# Filter_Bank_EVB.net
KiCad netlist of a schematic drawn in Altium Designer
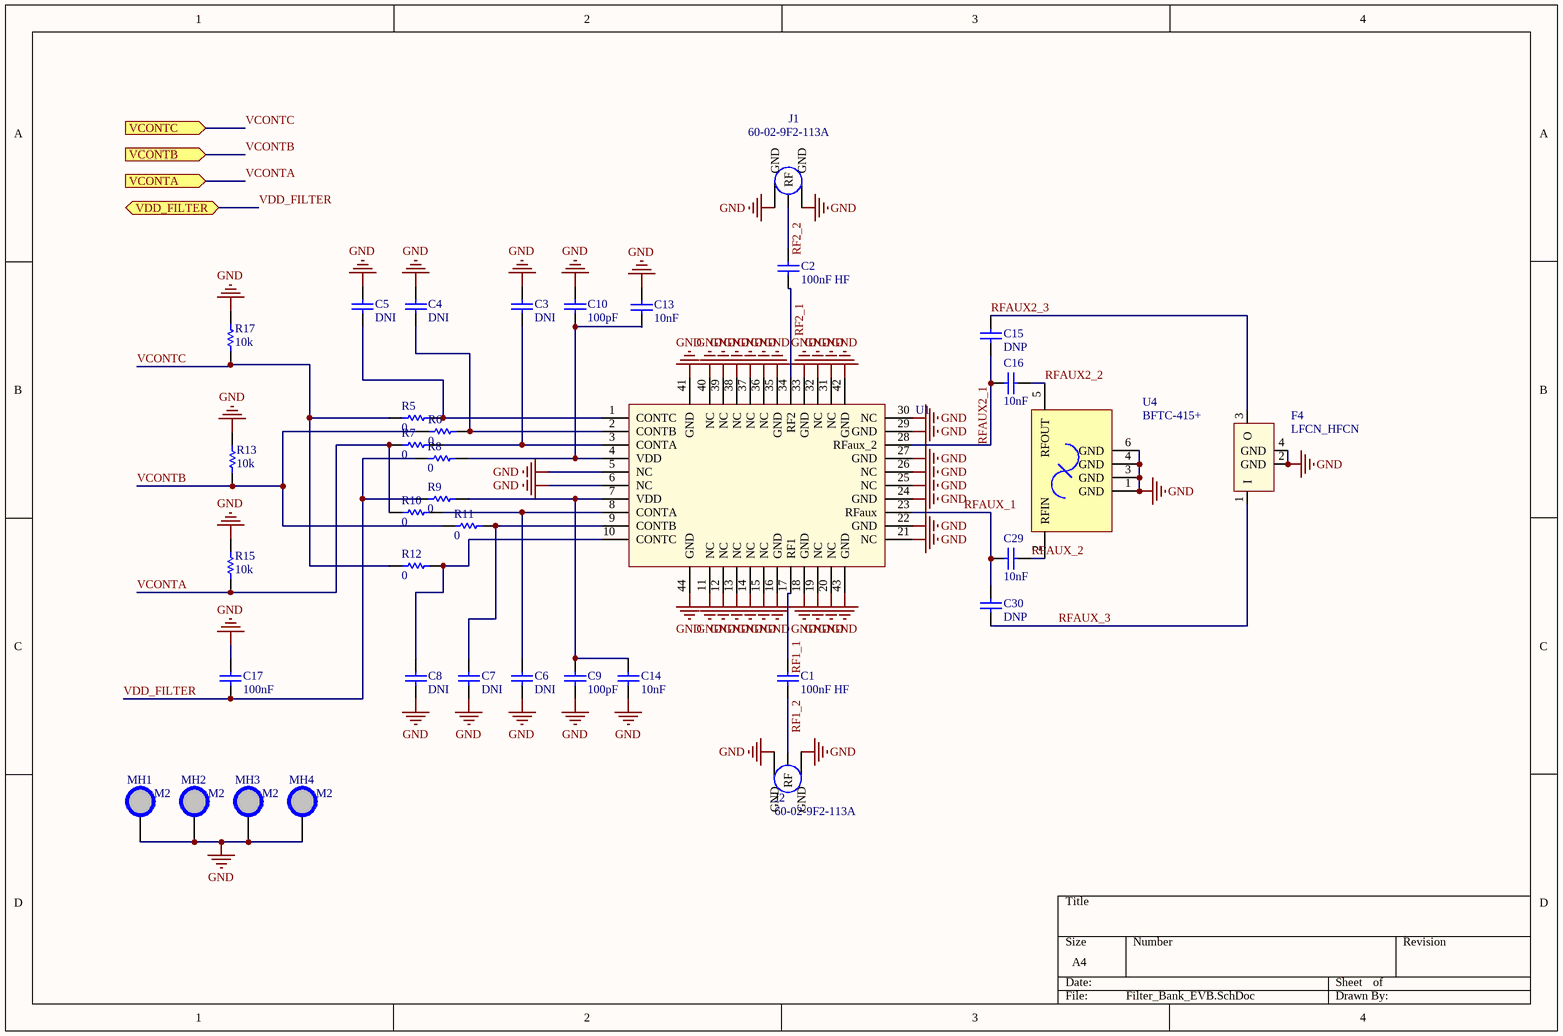
[diagram p0: Filter_Bank_EVB.SchDoc]

(export (version "E")
  (design (tool "Eeschema 10.0.6"))
  (components
    (comp (ref "C1")
      (value "100nF HF")
      (footprint "C0402")
      (description "Capacitor")
      (fields (field (name "Comment") "CAP"))
      (libsource (lib "ATEK") (part "CAP"))
    )
    (comp (ref "C2")
      (value "100nF HF")
      (footprint "C0402")
      (description "Capacitor")
      (fields (field (name "Comment") "CAP"))
      (libsource (lib "ATEK") (part "CAP"))
    )
    (comp (ref "C3")
      (value "DNI")
      (footprint "C0402")
      (description "Capacitor")
      (fields (field (name "Comment") "CAP"))
      (libsource (lib "ATEK") (part "CAP"))
    )
    (comp (ref "C4")
      (value "DNI")
      (footprint "C0402")
      (description "Capacitor")
      (fields (field (name "Comment") "CAP"))
      (libsource (lib "ATEK") (part "CAP"))
    )
    (comp (ref "C5")
      (value "DNI")
      (footprint "C0402")
      (description "Capacitor")
      (fields (field (name "Comment") "CAP"))
      (libsource (lib "ATEK") (part "CAP"))
    )
    (comp (ref "C6")
      (value "DNI")
      (footprint "C0402")
      (description "Capacitor")
      (fields (field (name "Comment") "CAP"))
      (libsource (lib "ATEK") (part "CAP"))
    )
    (comp (ref "C7")
      (value "DNI")
      (footprint "C0402")
      (description "Capacitor")
      (fields (field (name "Comment") "CAP"))
      (libsource (lib "ATEK") (part "CAP"))
    )
    (comp (ref "C8")
      (value "DNI")
      (footprint "C0402")
      (description "Capacitor")
      (fields (field (name "Comment") "CAP"))
      (libsource (lib "ATEK") (part "CAP"))
    )
    (comp (ref "C9")
      (value "100pF")
      (footprint "C0402")
      (description "Capacitor")
      (fields (field (name "Comment") "CAP"))
      (libsource (lib "ATEK") (part "CAP"))
    )
    (comp (ref "C10")
      (value "100pF")
      (footprint "C0402")
      (description "Capacitor")
      (fields (field (name "Comment") "CAP"))
      (libsource (lib "ATEK") (part "CAP"))
    )
    (comp (ref "C13")
      (value "10nF")
      (footprint "C0402")
      (description "Capacitor")
      (fields (field (name "Comment") "CAP"))
      (libsource (lib "ATEK") (part "CAP"))
    )
    (comp (ref "C14")
      (value "10nF")
      (footprint "C0402")
      (description "Capacitor")
      (fields (field (name "Comment") "CAP"))
      (libsource (lib "ATEK") (part "CAP"))
    )
    (comp (ref "C15")
      (value "DNP")
      (footprint "C0402")
      (description "Capacitor")
      (fields (field (name "Comment") "CAP"))
      (libsource (lib "ATEK") (part "CAP"))
    )
    (comp (ref "C16")
      (value "10nF")
      (footprint "C0402")
      (description "Capacitor")
      (fields (field (name "Comment") "CAP"))
      (libsource (lib "ATEK") (part "CAP"))
    )
    (comp (ref "C17")
      (value "100nF")
      (footprint "C0402")
      (description "Capacitor")
      (fields (field (name "Comment") "CAP"))
      (libsource (lib "ATEK") (part "CAP"))
    )
    (comp (ref "C29")
      (value "10nF")
      (footprint "C0402")
      (description "Capacitor")
      (fields (field (name "Comment") "CAP"))
      (libsource (lib "ATEK") (part "CAP"))
    )
    (comp (ref "C30")
      (value "DNP")
      (footprint "C0402")
      (description "Capacitor")
      (fields (field (name "Comment") "CAP"))
      (libsource (lib "ATEK") (part "CAP"))
    )
    (comp (ref "F4") (value "LFCN_HFCN") (footprint "FV1206") (libsource (lib "ATEK") (part "LFCN_HFCN")))
    (comp (ref "J1")
      (value "60-02-9F2-113A")
      (footprint "60-02-9F2-113A")
      (libsource (lib "ATEK") (part "60-02-9F2-113A"))
    )
    (comp (ref "J2")
      (value "60-02-9F2-113A")
      (footprint "60-02-9F2-113A")
      (libsource (lib "ATEK") (part "60-02-9F2-113A"))
    )
    (comp (ref "MH1") (value "M2") (footprint "M2") (libsource (lib "ATEK") (part "M2")))
    (comp (ref "MH2") (value "M2") (footprint "M2") (libsource (lib "ATEK") (part "M2")))
    (comp (ref "MH3") (value "M2") (footprint "M2") (libsource (lib "ATEK") (part "M2")))
    (comp (ref "MH4") (value "M2") (footprint "M2") (libsource (lib "ATEK") (part "M2")))
    (comp (ref "R5")
      (value "0")
      (footprint "R0402")
      (description "Resistor")
      (fields (field (name "Comment") "RES"))
      (libsource (lib "ATEK") (part "RES"))
    )
    (comp (ref "R6")
      (value "0")
      (footprint "R0402")
      (description "Resistor")
      (fields (field (name "Comment") "RES"))
      (libsource (lib "ATEK") (part "RES"))
    )
    (comp (ref "R7")
      (value "0")
      (footprint "R0402")
      (description "Resistor")
      (fields (field (name "Comment") "RES"))
      (libsource (lib "ATEK") (part "RES"))
    )
    (comp (ref "R8")
      (value "0")
      (footprint "R0402")
      (description "Resistor")
      (fields (field (name "Comment") "RES"))
      (libsource (lib "ATEK") (part "RES"))
    )
    (comp (ref "R9")
      (value "0")
      (footprint "R0402")
      (description "Resistor")
      (fields (field (name "Comment") "RES"))
      (libsource (lib "ATEK") (part "RES"))
    )
    (comp (ref "R10")
      (value "0")
      (footprint "R0402")
      (description "Resistor")
      (fields (field (name "Comment") "RES"))
      (libsource (lib "ATEK") (part "RES"))
    )
    (comp (ref "R11")
      (value "0")
      (footprint "R0402")
      (description "Resistor")
      (fields (field (name "Comment") "RES"))
      (libsource (lib "ATEK") (part "RES"))
    )
    (comp (ref "R12")
      (value "0")
      (footprint "R0402")
      (description "Resistor")
      (fields (field (name "Comment") "RES"))
      (libsource (lib "ATEK") (part "RES"))
    )
    (comp (ref "R13")
      (value "10k")
      (footprint "R0402")
      (description "Resistor")
      (fields (field (name "Comment") "RES"))
      (libsource (lib "ATEK") (part "RES"))
    )
    (comp (ref "R15")
      (value "10k")
      (footprint "R0402")
      (description "Resistor")
      (fields (field (name "Comment") "RES"))
      (libsource (lib "ATEK") (part "RES"))
    )
    (comp (ref "R17")
      (value "10k")
      (footprint "R0402")
      (description "Resistor")
      (fields (field (name "Comment") "RES"))
      (libsource (lib "ATEK") (part "RES"))
    )
    (comp (ref "U1")
      (value "Bypass LNA")
      (footprint "40L-QFN-6X6-50P-MOD")
      (libsource (lib "ATEK") (part "Filter_Bank"))
    )
    (comp (ref "U4") (value "BFTC-415+") (footprint "BFTC-415+") (libsource (lib "ATEK") (part "BFTC-415+")))
  )
  (nets
    (net (code "1") (name "/RF1_1") (class "Default")
      (node (ref "C1") (pin "2") (pinfunction "2_2") (pintype "passive"))
      (node (ref "U1") (pin "17") (pinfunction "RF1_17") (pintype "passive"))
    )
    (net (code "2") (name "/RF1_2") (class "Default")
      (node (ref "C1") (pin "1") (pinfunction "1_1") (pintype "passive"))
      (node (ref "J2") (pin "1") (pinfunction "RF_1") (pintype "passive"))
    )
    (net (code "3") (name "/RF2_1") (class "Default")
      (node (ref "C2") (pin "1") (pinfunction "1_1") (pintype "passive"))
      (node (ref "U1") (pin "34") (pinfunction "RF2_34") (pintype "passive"))
    )
    (net (code "4") (name "/RF2_2") (class "Default")
      (node (ref "C2") (pin "2") (pinfunction "2_2") (pintype "passive"))
      (node (ref "J1") (pin "1") (pinfunction "RF_1") (pintype "passive"))
    )
    (net (code "5") (name "/RFAUX2_1") (class "Default")
      (node (ref "C15") (pin "2") (pinfunction "2_2") (pintype "passive"))
      (node (ref "C16") (pin "2") (pinfunction "2_2") (pintype "passive"))
      (node (ref "U1") (pin "28") (pinfunction "RFaux_2_28") (pintype "passive"))
    )
    (net (code "6") (name "/RFAUX2_2") (class "Default")
      (node (ref "C16") (pin "1") (pinfunction "1_1") (pintype "passive"))
      (node (ref "U4") (pin "5") (pinfunction "RFOUT_5") (pintype "passive"))
    )
    (net (code "7") (name "/RFAUX2_3") (class "Default")
      (node (ref "C15") (pin "1") (pinfunction "1_1") (pintype "passive"))
      (node (ref "F4") (pin "3") (pinfunction "O_3") (pintype "passive"))
    )
    (net (code "8") (name "/RFAUX_1") (class "Default")
      (node (ref "C29") (pin "2") (pinfunction "2_2") (pintype "passive"))
      (node (ref "C30") (pin "1") (pinfunction "1_1") (pintype "passive"))
      (node (ref "U1") (pin "23") (pinfunction "RFaux_23") (pintype "passive"))
    )
    (net (code "9") (name "/RFAUX_2") (class "Default")
      (node (ref "C29") (pin "1") (pinfunction "1_1") (pintype "passive"))
      (node (ref "U4") (pin "2") (pinfunction "RFIN_2") (pintype "passive"))
    )
    (net (code "10") (name "/RFAUX_3") (class "Default")
      (node (ref "C30") (pin "2") (pinfunction "2_2") (pintype "passive"))
      (node (ref "F4") (pin "1") (pinfunction "I_1") (pintype "passive"))
    )
    (net (code "11") (name "/VCONTA") (class "Default")
      (node (ref "R10") (pin "1") (pinfunction "1_1") (pintype "passive"))
      (node (ref "R15") (pin "1") (pinfunction "1_1") (pintype "passive"))
      (node (ref "R7") (pin "1") (pinfunction "1_1") (pintype "passive"))
    )
    (net (code "12") (name "/VCONTB") (class "Default")
      (node (ref "R11") (pin "1") (pinfunction "1_1") (pintype "passive"))
      (node (ref "R13") (pin "1") (pinfunction "1_1") (pintype "passive"))
      (node (ref "R6") (pin "1") (pinfunction "1_1") (pintype "passive"))
    )
    (net (code "13") (name "/VCONTC") (class "Default")
      (node (ref "R12") (pin "1") (pinfunction "1_1") (pintype "passive"))
      (node (ref "R17") (pin "1") (pinfunction "1_1") (pintype "passive"))
      (node (ref "R5") (pin "1") (pinfunction "1_1") (pintype "passive"))
    )
    (net (code "14") (name "/VDD_FILTER") (class "Default")
      (node (ref "C17") (pin "1") (pinfunction "1_1") (pintype "passive"))
      (node (ref "R8") (pin "1") (pinfunction "1_1") (pintype "passive"))
      (node (ref "R9") (pin "1") (pinfunction "1_1") (pintype "passive"))
    )
    (net (code "15") (name "GND") (class "Default")
      (node (ref "C10") (pin "2") (pinfunction "2_2") (pintype "passive"))
      (node (ref "C13") (pin "1") (pinfunction "1_1") (pintype "passive"))
      (node (ref "C14") (pin "1") (pinfunction "1_1") (pintype "passive"))
      (node (ref "C17") (pin "2") (pinfunction "2_2") (pintype "passive"))
      (node (ref "C3") (pin "2") (pinfunction "2_2") (pintype "passive"))
      (node (ref "C4") (pin "2") (pinfunction "2_2") (pintype "passive"))
      (node (ref "C5") (pin "2") (pinfunction "2_2") (pintype "passive"))
      (node (ref "C6") (pin "1") (pinfunction "1_1") (pintype "passive"))
      (node (ref "C7") (pin "1") (pinfunction "1_1") (pintype "passive"))
      (node (ref "C8") (pin "1") (pinfunction "1_1") (pintype "passive"))
      (node (ref "C9") (pin "1") (pinfunction "1_1") (pintype "passive"))
      (node (ref "F4") (pin "2") (pinfunction "GND_2") (pintype "passive"))
      (node (ref "F4") (pin "4") (pinfunction "GND_4") (pintype "passive"))
      (node (ref "J1") (pin "2") (pinfunction "GND_2") (pintype "passive"))
      (node (ref "J2") (pin "2") (pinfunction "GND_2") (pintype "passive"))
      (node (ref "MH1") (pin "1") (pinfunction "1_1") (pintype "passive"))
      (node (ref "MH2") (pin "1") (pinfunction "1_1") (pintype "passive"))
      (node (ref "MH3") (pin "1") (pinfunction "1_1") (pintype "passive"))
      (node (ref "MH4") (pin "1") (pinfunction "1_1") (pintype "passive"))
      (node (ref "R13") (pin "2") (pinfunction "2_2") (pintype "passive"))
      (node (ref "R15") (pin "2") (pinfunction "2_2") (pintype "passive"))
      (node (ref "R17") (pin "2") (pinfunction "2_2") (pintype "passive"))
      (node (ref "U1") (pin "11") (pinfunction "NC_11") (pintype "passive"))
      (node (ref "U1") (pin "12") (pinfunction "NC_12") (pintype "passive"))
      (node (ref "U1") (pin "13") (pinfunction "NC_13") (pintype "passive"))
      (node (ref "U1") (pin "14") (pinfunction "NC_14") (pintype "passive"))
      (node (ref "U1") (pin "15") (pinfunction "NC_15") (pintype "passive"))
      (node (ref "U1") (pin "16") (pinfunction "GND_16") (pintype "passive"))
      (node (ref "U1") (pin "18") (pinfunction "GND_18") (pintype "passive"))
      (node (ref "U1") (pin "19") (pinfunction "NC_19") (pintype "passive"))
      (node (ref "U1") (pin "20") (pinfunction "NC_20") (pintype "passive"))
      (node (ref "U1") (pin "21") (pinfunction "NC_21") (pintype "passive"))
      (node (ref "U1") (pin "22") (pinfunction "GND_22") (pintype "passive"))
      (node (ref "U1") (pin "24") (pinfunction "GND_24") (pintype "passive"))
      (node (ref "U1") (pin "25") (pinfunction "NC_25") (pintype "passive"))
      (node (ref "U1") (pin "26") (pinfunction "NC_26") (pintype "passive"))
      (node (ref "U1") (pin "27") (pinfunction "GND_27") (pintype "passive"))
      (node (ref "U1") (pin "29") (pinfunction "GND_29") (pintype "passive"))
      (node (ref "U1") (pin "30") (pinfunction "NC_30") (pintype "passive"))
      (node (ref "U1") (pin "31") (pinfunction "NC_31") (pintype "passive"))
      (node (ref "U1") (pin "32") (pinfunction "NC_32") (pintype "passive"))
      (node (ref "U1") (pin "33") (pinfunction "GND_33") (pintype "passive"))
      (node (ref "U1") (pin "35") (pinfunction "GND_35") (pintype "passive"))
      (node (ref "U1") (pin "36") (pinfunction "NC_36") (pintype "passive"))
      (node (ref "U1") (pin "37") (pinfunction "NC_37") (pintype "passive"))
      (node (ref "U1") (pin "38") (pinfunction "NC_38") (pintype "passive"))
      (node (ref "U1") (pin "39") (pinfunction "NC_39") (pintype "passive"))
      (node (ref "U1") (pin "40") (pinfunction "NC_40") (pintype "passive"))
      (node (ref "U1") (pin "41") (pinfunction "GND_41") (pintype "passive"))
      (node (ref "U1") (pin "42") (pinfunction "GND_42") (pintype "passive"))
      (node (ref "U1") (pin "43") (pinfunction "GND_43") (pintype "passive"))
      (node (ref "U1") (pin "44") (pinfunction "GND_44") (pintype "passive"))
      (node (ref "U1") (pin "5") (pinfunction "NC_5") (pintype "passive"))
      (node (ref "U1") (pin "6") (pinfunction "NC_6") (pintype "passive"))
      (node (ref "U4") (pin "1") (pinfunction "GND_1") (pintype "passive"))
      (node (ref "U4") (pin "3") (pinfunction "GND_3") (pintype "passive"))
      (node (ref "U4") (pin "4") (pinfunction "GND_4") (pintype "passive"))
      (node (ref "U4") (pin "6") (pinfunction "GND_6") (pintype "passive"))
    )
    (net (code "16") (name "Net-(C3-Pad1)") (class "Default")
      (node (ref "C3") (pin "1") (pinfunction "1_1") (pintype "passive"))
      (node (ref "R7") (pin "2") (pinfunction "2_2") (pintype "passive"))
      (node (ref "U1") (pin "3") (pinfunction "CONTA_3") (pintype "passive"))
    )
    (net (code "17") (name "Net-(C4-Pad1)") (class "Default")
      (node (ref "C4") (pin "1") (pinfunction "1_1") (pintype "passive"))
      (node (ref "R6") (pin "2") (pinfunction "2_2") (pintype "passive"))
      (node (ref "U1") (pin "2") (pinfunction "CONTB_2") (pintype "passive"))
    )
    (net (code "18") (name "Net-(C5-Pad1)") (class "Default")
      (node (ref "C5") (pin "1") (pinfunction "1_1") (pintype "passive"))
      (node (ref "R5") (pin "2") (pinfunction "2_2") (pintype "passive"))
      (node (ref "U1") (pin "1") (pinfunction "CONTC_1") (pintype "passive"))
    )
    (net (code "19") (name "Net-(C6-Pad2)") (class "Default")
      (node (ref "C6") (pin "2") (pinfunction "2_2") (pintype "passive"))
      (node (ref "R10") (pin "2") (pinfunction "2_2") (pintype "passive"))
      (node (ref "U1") (pin "8") (pinfunction "CONTA_8") (pintype "passive"))
    )
    (net (code "20") (name "Net-(C7-Pad2)") (class "Default")
      (node (ref "C7") (pin "2") (pinfunction "2_2") (pintype "passive"))
      (node (ref "R11") (pin "2") (pinfunction "2_2") (pintype "passive"))
      (node (ref "U1") (pin "9") (pinfunction "CONTB_9") (pintype "passive"))
    )
    (net (code "21") (name "Net-(C8-Pad2)") (class "Default")
      (node (ref "C8") (pin "2") (pinfunction "2_2") (pintype "passive"))
      (node (ref "R12") (pin "2") (pinfunction "2_2") (pintype "passive"))
      (node (ref "U1") (pin "10") (pinfunction "CONTC_10") (pintype "passive"))
    )
    (net (code "22") (name "Net-(C10-Pad1)") (class "Default")
      (node (ref "C10") (pin "1") (pinfunction "1_1") (pintype "passive"))
      (node (ref "C13") (pin "2") (pinfunction "2_2") (pintype "passive"))
      (node (ref "R8") (pin "2") (pinfunction "2_2") (pintype "passive"))
      (node (ref "U1") (pin "4") (pinfunction "VDD_4") (pintype "passive"))
    )
    (net (code "23") (name "Net-(C14-Pad2)") (class "Default")
      (node (ref "C14") (pin "2") (pinfunction "2_2") (pintype "passive"))
      (node (ref "C9") (pin "2") (pinfunction "2_2") (pintype "passive"))
      (node (ref "R9") (pin "2") (pinfunction "2_2") (pintype "passive"))
      (node (ref "U1") (pin "7") (pinfunction "VDD_7") (pintype "passive"))
    )
  )
)
